# Me-Bluetooth_v2_0.net
KiCad netlist of a schematic drawn in EAGLE
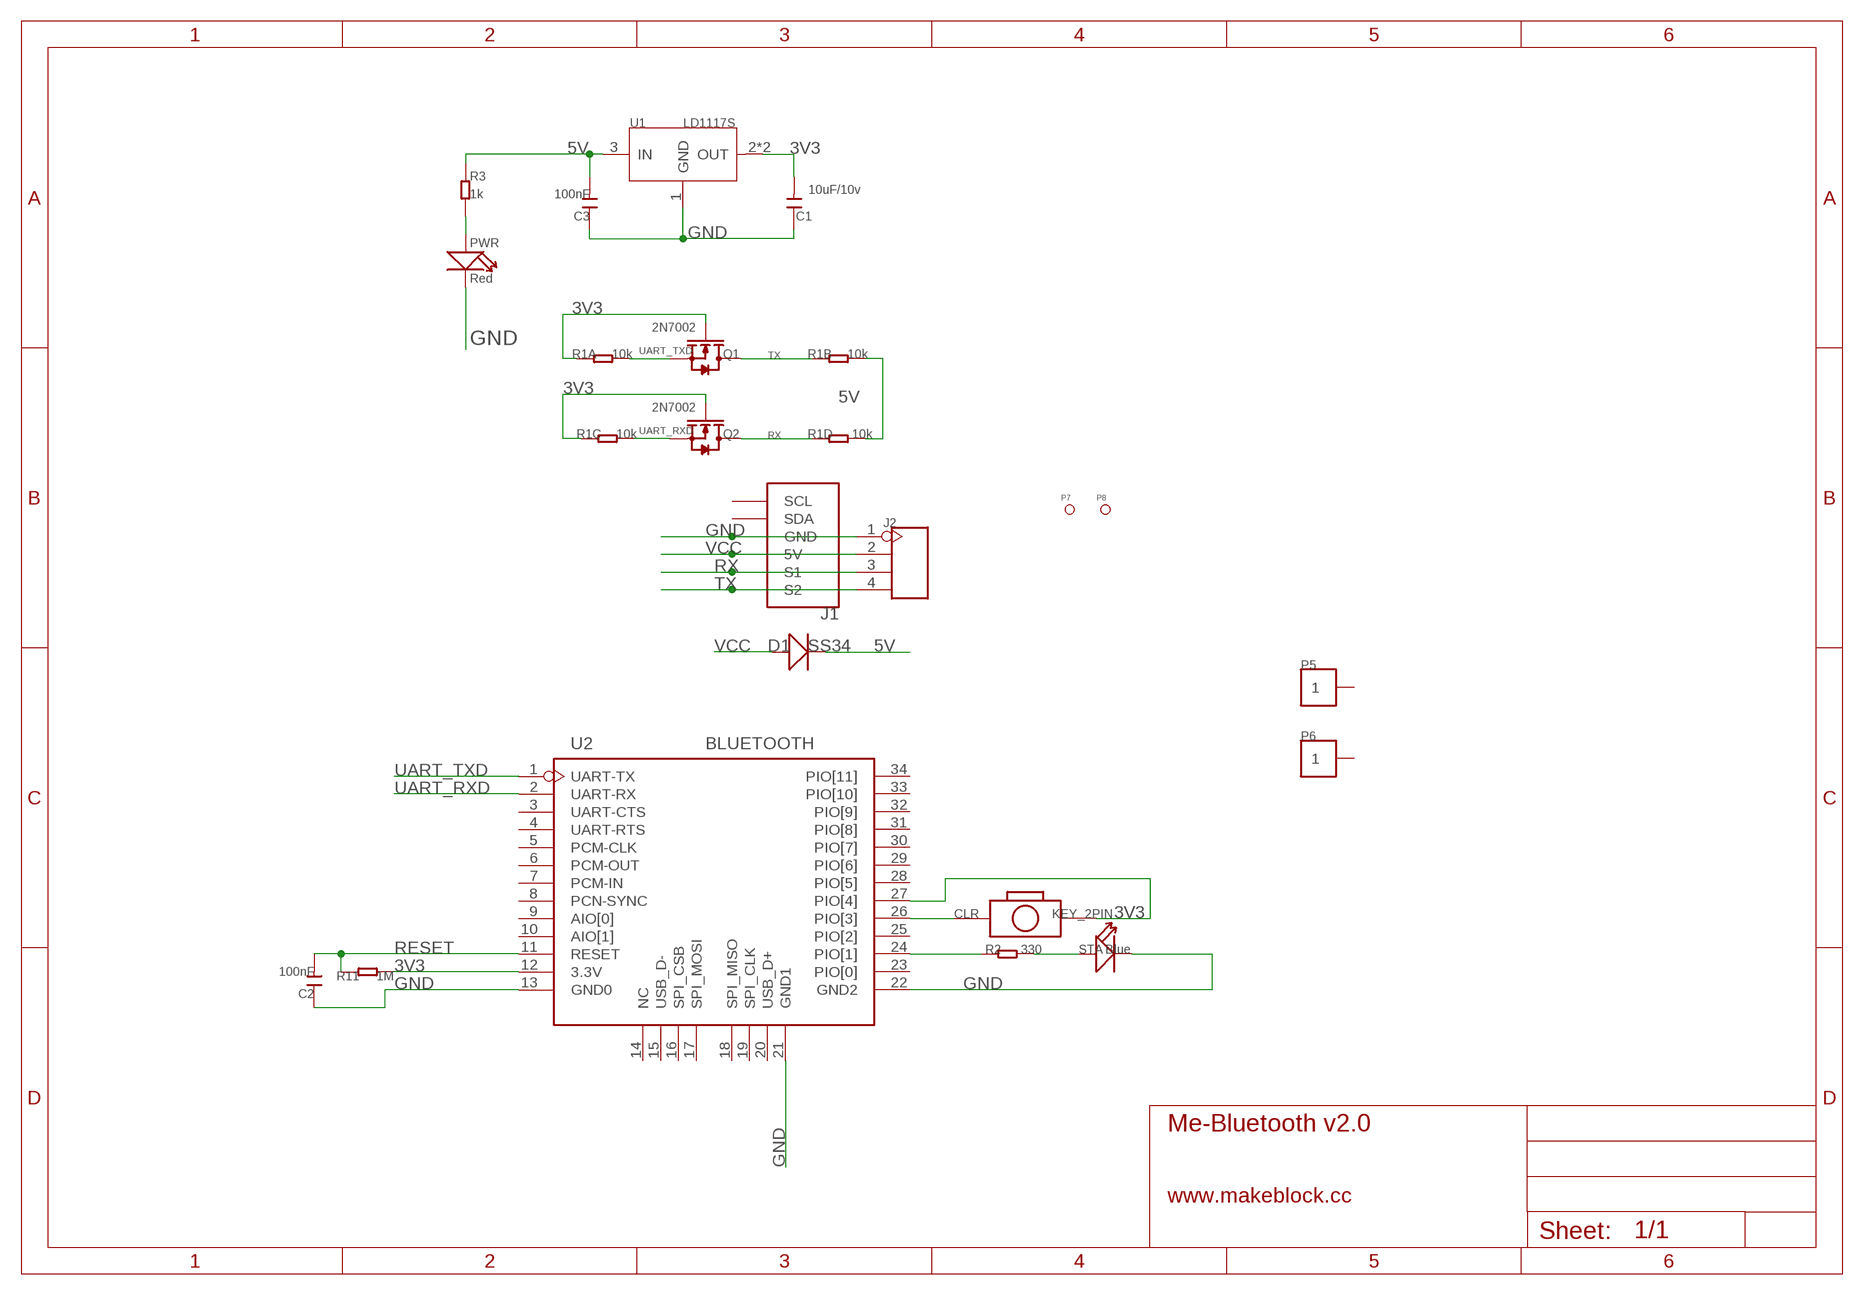
[diagram p0: schematic, sheet 1]

(export (version "E")
  (design (tool "Eeschema 10.0.6"))
  (components
    (comp (ref "C1")
      (value "10uF/10v")
      (footprint "eagle-import:0603")
      (libsource (lib "eagle-import") (part "C-0603"))
    )
    (comp (ref "C2")
      (value "100nF")
      (footprint "eagle-import:0603")
      (libsource (lib "eagle-import") (part "C-0603"))
    )
    (comp (ref "C3")
      (value "100nF")
      (footprint "eagle-import:0603")
      (libsource (lib "eagle-import") (part "C-0603"))
    )
    (comp (ref "CLR")
      (value "KEY_2PIN")
      (footprint "eagle-import:KEY_2PIN")
      (libsource (lib "eagle-import") (part "KEY_2PIN"))
    )
    (comp (ref "D1")
      (value "SS34")
      (footprint "eagle-import:D2010")
      (libsource (lib "eagle-import") (part "D'SMA'"))
    )
    (comp (ref "J1")
      (value "RJ11-6P6C-DIGI")
      (footprint "eagle-import:RJ11-6P6C")
      (libsource (lib "eagle-import") (part "RJ11-6P6C-DIGI"))
    )
    (comp (ref "J2")
      (value "HEADER-4P-60/35MIL")
      (footprint "eagle-import:4P-65_35MIL")
      (libsource (lib "eagle-import") (part "HEADER-4P-60/35MIL"))
    )
    (comp (ref "P5")
      (value "PAD-1P-4MM")
      (footprint "eagle-import:HOLE-01")
      (libsource (lib "eagle-import") (part "PAD-1P-4MM"))
    )
    (comp (ref "P6")
      (value "PAD-1P-4MM")
      (footprint "eagle-import:HOLE-01")
      (libsource (lib "eagle-import") (part "PAD-1P-4MM"))
    )
    (comp (ref "P7")
      (value "PAD-MARK")
      (footprint "eagle-import:ROUND-MARK-1.0")
      (fields (field (name "PARTNO") "DNP"))
      (libsource (lib "eagle-import") (part "PAD-MARK"))
    )
    (comp (ref "P8")
      (value "PAD-MARK")
      (footprint "eagle-import:ROUND-MARK-1.0")
      (fields (field (name "PARTNO") "DNP"))
      (libsource (lib "eagle-import") (part "PAD-MARK"))
    )
    (comp (ref "PWR")
      (value "Red")
      (footprint "eagle-import:LED-0603")
      (libsource (lib "eagle-import") (part "LED'0603'"))
    )
    (comp (ref "Q1")
      (value "2N7002")
      (footprint "eagle-import:2N7002")
      (libsource (lib "eagle-import") (part "2N7002"))
    )
    (comp (ref "Q2")
      (value "2N7002")
      (footprint "eagle-import:2N7002")
      (libsource (lib "eagle-import") (part "2N7002"))
    )
    (comp (ref "R1")
      (value "10k")
      (footprint "eagle-import:1206-8-3.3X2.4")
      (libsource (lib "eagle-import") (part "R-4R-1206"))
    )
    (comp (ref "R2")
      (value "330")
      (footprint "eagle-import:0603")
      (libsource (lib "eagle-import") (part "R-0603"))
    )
    (comp (ref "R3")
      (value "1k")
      (footprint "eagle-import:0603")
      (libsource (lib "eagle-import") (part "R-0603"))
    )
    (comp (ref "R11")
      (value "1M")
      (footprint "eagle-import:0603")
      (libsource (lib "eagle-import") (part "R-0603"))
    )
    (comp (ref "STA")
      (value "Blue")
      (footprint "eagle-import:LED-0603")
      (libsource (lib "eagle-import") (part "LED'0603'"))
    )
    (comp (ref "U1")
      (value "LD1117S")
      (footprint "eagle-import:SOT-223")
      (libsource (lib "eagle-import") (part "LD1117S"))
    )
    (comp (ref "U2")
      (value "BLUETOOTH")
      (footprint "eagle-import:BLUETOOTH")
      (libsource (lib "eagle-import") (part "BLUETOOTH"))
    )
  )
  (nets
    (net (code "1") (name "/3V3") (class "Default")
      (node (ref "C1") (pin "2") (pinfunction "2_2") (pintype "passive"))
      (node (ref "CLR") (pin "P$2") (pinfunction "2_P$2") (pintype "bidirectional"))
      (node (ref "Q1") (pin "1") (pinfunction "G_1") (pintype "passive"))
      (node (ref "Q2") (pin "1") (pinfunction "G_1") (pintype "passive"))
      (node (ref "R1") (pin "1") (pinfunction "1_1") (pintype "passive"))
      (node (ref "R1") (pin "3") (pinfunction "1_3") (pintype "passive"))
      (node (ref "R11") (pin "2") (pinfunction "2_2") (pintype "passive"))
      (node (ref "U1") (pin "2") (pinfunction "OUT_2") (pintype "bidirectional"))
      (node (ref "U1") (pin "TER") (pinfunction "OUT_TER") (pintype "bidirectional"))
      (node (ref "U2") (pin "12") (pinfunction "3.3V_12") (pintype "bidirectional"))
      (node (ref "U2") (pin "27") (pinfunction "PIO[4]_27") (pintype "bidirectional"))
    )
    (net (code "2") (name "/5V") (class "Default")
      (node (ref "C3") (pin "2") (pinfunction "2_2") (pintype "passive"))
      (node (ref "D1") (pin "-") (pinfunction "-_-") (pintype "passive"))
      (node (ref "R1") (pin "5") (pinfunction "2_5") (pintype "passive"))
      (node (ref "R1") (pin "7") (pinfunction "2_7") (pintype "passive"))
      (node (ref "R3") (pin "1") (pinfunction "1_1") (pintype "passive"))
      (node (ref "U1") (pin "3") (pinfunction "IN_3") (pintype "bidirectional"))
    )
    (net (code "3") (name "/GND") (class "Default")
      (node (ref "C1") (pin "1") (pinfunction "1_1") (pintype "passive"))
      (node (ref "C2") (pin "1") (pinfunction "1_1") (pintype "passive"))
      (node (ref "C3") (pin "1") (pinfunction "1_1") (pintype "passive"))
      (node (ref "J1") (pin "3") (pinfunction "GND_3") (pintype "bidirectional"))
      (node (ref "J2") (pin "1") (pinfunction "P$1_1") (pintype "bidirectional"))
      (node (ref "PWR") (pin "-") (pinfunction "-_-") (pintype "passive"))
      (node (ref "STA") (pin "-") (pinfunction "-_-") (pintype "passive"))
      (node (ref "U1") (pin "1") (pinfunction "GND_1") (pintype "bidirectional"))
      (node (ref "U2") (pin "13") (pinfunction "GND0_13") (pintype "bidirectional"))
      (node (ref "U2") (pin "21") (pinfunction "GND1_21") (pintype "bidirectional"))
      (node (ref "U2") (pin "22") (pinfunction "GND2_22") (pintype "bidirectional"))
    )
    (net (code "4") (name "/RESET") (class "Default")
      (node (ref "C2") (pin "2") (pinfunction "2_2") (pintype "passive"))
      (node (ref "R11") (pin "1") (pinfunction "1_1") (pintype "passive"))
      (node (ref "U2") (pin "11") (pinfunction "RESET_11") (pintype "bidirectional"))
    )
    (net (code "5") (name "/RX") (class "Default")
      (node (ref "J1") (pin "5") (pinfunction "S1_5") (pintype "bidirectional"))
      (node (ref "J2") (pin "3") (pinfunction "P$3_3") (pintype "bidirectional"))
      (node (ref "Q2") (pin "3") (pinfunction "D_3") (pintype "passive"))
      (node (ref "R1") (pin "4") (pinfunction "1_4") (pintype "passive"))
    )
    (net (code "6") (name "/TX") (class "Default")
      (node (ref "J1") (pin "6") (pinfunction "S2_6") (pintype "bidirectional"))
      (node (ref "J2") (pin "4") (pinfunction "P$4_4") (pintype "bidirectional"))
      (node (ref "Q1") (pin "3") (pinfunction "D_3") (pintype "passive"))
      (node (ref "R1") (pin "2") (pinfunction "1_2") (pintype "passive"))
    )
    (net (code "7") (name "/UART_RXD") (class "Default")
      (node (ref "Q2") (pin "2") (pinfunction "S_2") (pintype "passive"))
      (node (ref "R1") (pin "6") (pinfunction "2_6") (pintype "passive"))
      (node (ref "U2") (pin "2") (pinfunction "UART-RX_2") (pintype "bidirectional"))
    )
    (net (code "8") (name "/UART_TXD") (class "Default")
      (node (ref "Q1") (pin "2") (pinfunction "S_2") (pintype "passive"))
      (node (ref "R1") (pin "8") (pinfunction "2_8") (pintype "passive"))
      (node (ref "U2") (pin "1") (pinfunction "UART-TX_1") (pintype "bidirectional"))
    )
    (net (code "9") (name "/VCC") (class "Default")
      (node (ref "D1") (pin "+") (pinfunction "+_+") (pintype "passive"))
      (node (ref "J1") (pin "4") (pinfunction "5V_4") (pintype "bidirectional"))
      (node (ref "J2") (pin "2") (pinfunction "P$2_2") (pintype "bidirectional"))
    )
    (net (code "10") (name "Net-(PWR-Pad+)") (class "Default")
      (node (ref "PWR") (pin "+") (pinfunction "+_+") (pintype "passive"))
      (node (ref "R3") (pin "2") (pinfunction "2_2") (pintype "passive"))
    )
    (net (code "11") (name "Net-(R2-Pad2)") (class "Default")
      (node (ref "R2") (pin "2") (pinfunction "2_2") (pintype "passive"))
      (node (ref "STA") (pin "+") (pinfunction "+_+") (pintype "passive"))
    )
    (net (code "12") (name "Net-(U2-PIO[1])") (class "Default")
      (node (ref "R2") (pin "1") (pinfunction "1_1") (pintype "passive"))
      (node (ref "U2") (pin "24") (pinfunction "PIO[1]_24") (pintype "bidirectional"))
    )
    (net (code "13") (name "Net-(U2-PIO[3])") (class "Default")
      (node (ref "CLR") (pin "1") (pinfunction "1_1") (pintype "bidirectional"))
      (node (ref "U2") (pin "26") (pinfunction "PIO[3]_26") (pintype "bidirectional"))
    )
    (net (code "14") (name "unconnected-(J1-SCL-Pad1)") (class "Default")
      (node (ref "J1") (pin "1") (pinfunction "SCL_1") (pintype "bidirectional"))
    )
    (net (code "15") (name "unconnected-(J1-SDA-Pad2)") (class "Default")
      (node (ref "J1") (pin "2") (pinfunction "SDA_2") (pintype "bidirectional"))
    )
    (net (code "16") (name "unconnected-(P5-Pad1)") (class "Default")
      (node (ref "P5") (pin "1") (pinfunction "1_1") (pintype "bidirectional"))
    )
    (net (code "17") (name "unconnected-(P6-Pad1)") (class "Default")
      (node (ref "P6") (pin "1") (pinfunction "1_1") (pintype "bidirectional"))
    )
    (net (code "18") (name "unconnected-(U2-AIO[0]-Pad9)") (class "Default")
      (node (ref "U2") (pin "9") (pinfunction "AIO[0]_9") (pintype "bidirectional"))
    )
    (net (code "19") (name "unconnected-(U2-AIO[1]-Pad10)") (class "Default")
      (node (ref "U2") (pin "10") (pinfunction "AIO[1]_10") (pintype "bidirectional"))
    )
    (net (code "20") (name "unconnected-(U2-NC-Pad14)") (class "Default")
      (node (ref "U2") (pin "14") (pinfunction "NC_14") (pintype "bidirectional"))
    )
    (net (code "21") (name "unconnected-(U2-PCM-CLK-Pad5)") (class "Default")
      (node (ref "U2") (pin "5") (pinfunction "PCM-CLK_5") (pintype "bidirectional"))
    )
    (net (code "22") (name "unconnected-(U2-PCM-IN-Pad7)") (class "Default")
      (node (ref "U2") (pin "7") (pinfunction "PCM-IN_7") (pintype "bidirectional"))
    )
    (net (code "23") (name "unconnected-(U2-PCM-OUT-Pad6)") (class "Default")
      (node (ref "U2") (pin "6") (pinfunction "PCM-OUT_6") (pintype "bidirectional"))
    )
    (net (code "24") (name "unconnected-(U2-PCN-SYNC-Pad8)") (class "Default")
      (node (ref "U2") (pin "8") (pinfunction "PCN-SYNC_8") (pintype "bidirectional"))
    )
    (net (code "25") (name "unconnected-(U2-PIO[0]-Pad23)") (class "Default")
      (node (ref "U2") (pin "23") (pinfunction "PIO[0]_23") (pintype "bidirectional"))
    )
    (net (code "26") (name "unconnected-(U2-PIO[2]-Pad25)") (class "Default")
      (node (ref "U2") (pin "25") (pinfunction "PIO[2]_25") (pintype "bidirectional"))
    )
    (net (code "27") (name "unconnected-(U2-PIO[5]-Pad28)") (class "Default")
      (node (ref "U2") (pin "28") (pinfunction "PIO[5]_28") (pintype "bidirectional"))
    )
    (net (code "28") (name "unconnected-(U2-PIO[6]-Pad29)") (class "Default")
      (node (ref "U2") (pin "29") (pinfunction "PIO[6]_29") (pintype "bidirectional"))
    )
    (net (code "29") (name "unconnected-(U2-PIO[7]-Pad30)") (class "Default")
      (node (ref "U2") (pin "30") (pinfunction "PIO[7]_30") (pintype "bidirectional"))
    )
    (net (code "30") (name "unconnected-(U2-PIO[8]-Pad31)") (class "Default")
      (node (ref "U2") (pin "31") (pinfunction "PIO[8]_31") (pintype "bidirectional"))
    )
    (net (code "31") (name "unconnected-(U2-PIO[9]-Pad32)") (class "Default")
      (node (ref "U2") (pin "32") (pinfunction "PIO[9]_32") (pintype "bidirectional"))
    )
    (net (code "32") (name "unconnected-(U2-PIO[10]-Pad33)") (class "Default")
      (node (ref "U2") (pin "33") (pinfunction "PIO[10]_33") (pintype "bidirectional"))
    )
    (net (code "33") (name "unconnected-(U2-PIO[11]-Pad34)") (class "Default")
      (node (ref "U2") (pin "34") (pinfunction "PIO[11]_34") (pintype "bidirectional"))
    )
    (net (code "34") (name "unconnected-(U2-SPI_CLK-Pad19)") (class "Default")
      (node (ref "U2") (pin "19") (pinfunction "SPI_CLK_19") (pintype "bidirectional"))
    )
    (net (code "35") (name "unconnected-(U2-SPI_CSB-Pad16)") (class "Default")
      (node (ref "U2") (pin "16") (pinfunction "SPI_CSB_16") (pintype "bidirectional"))
    )
    (net (code "36") (name "unconnected-(U2-SPI_MISO-Pad18)") (class "Default")
      (node (ref "U2") (pin "18") (pinfunction "SPI_MISO_18") (pintype "bidirectional"))
    )
    (net (code "37") (name "unconnected-(U2-SPI_MOSI-Pad17)") (class "Default")
      (node (ref "U2") (pin "17") (pinfunction "SPI_MOSI_17") (pintype "bidirectional"))
    )
    (net (code "38") (name "unconnected-(U2-UART-CTS-Pad3)") (class "Default")
      (node (ref "U2") (pin "3") (pinfunction "UART-CTS_3") (pintype "bidirectional"))
    )
    (net (code "39") (name "unconnected-(U2-UART-RTS-Pad4)") (class "Default")
      (node (ref "U2") (pin "4") (pinfunction "UART-RTS_4") (pintype "bidirectional"))
    )
    (net (code "40") (name "unconnected-(U2-USB_D+-Pad20)") (class "Default")
      (node (ref "U2") (pin "20") (pinfunction "USB_D+_20") (pintype "bidirectional"))
    )
    (net (code "41") (name "unconnected-(U2-USB_D--Pad15)") (class "Default")
      (node (ref "U2") (pin "15") (pinfunction "USB_D-_15") (pintype "bidirectional"))
    )
  )
)
